# PSU12V-250mA-Protection.net
KiCad netlist of a schematic drawn in Altium Designer
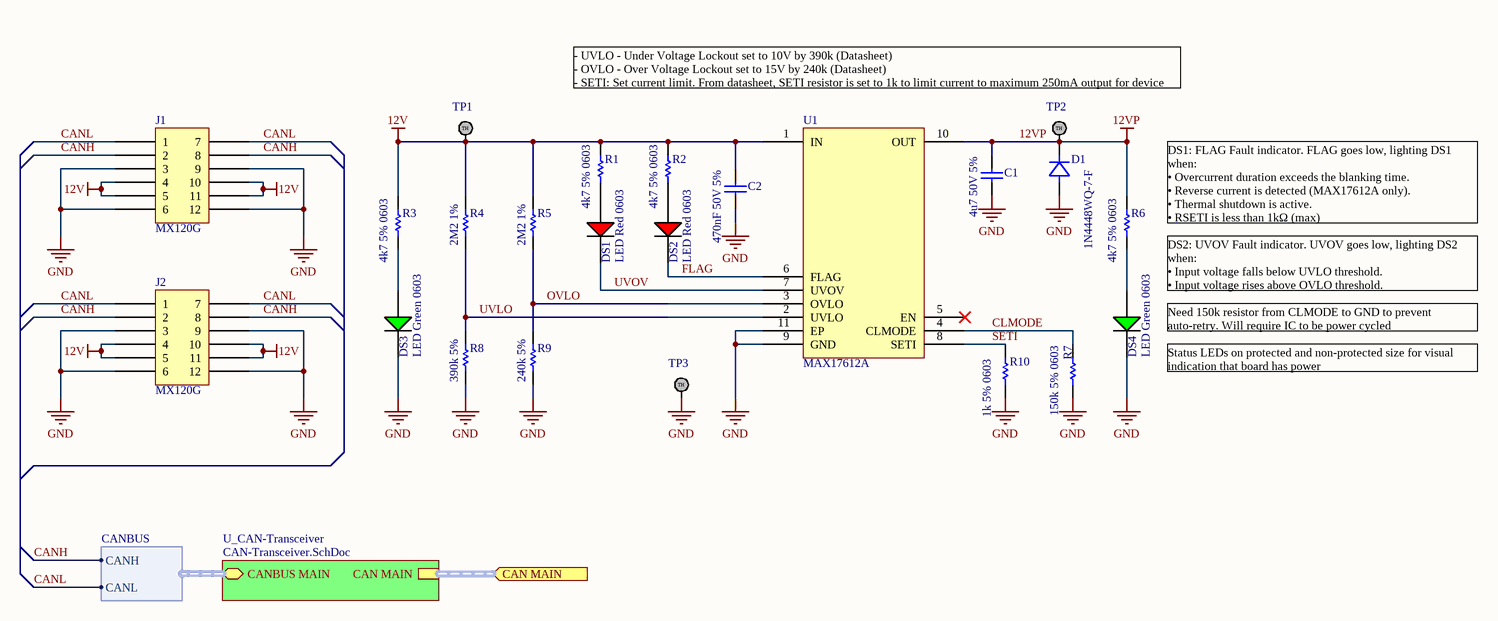
[diagram p0: PSU12V-250mA-Protection.SchDoc]

(export (version "E")
  (design (tool "Eeschema 10.0.6"))
  (components
    (comp (ref "C1")
      (value "4u7 50V 5%")
      (footprint "Cap_Ceramic_0603")
      (description "Capacitor, Ceramic, SMD, 4u7, 50V, 5%, X7R, 0603")
      (libsource (lib "StandardCapacitors") (part "4u7 50V 5% X7R 0603"))
    )
    (comp (ref "C2")
      (value "470nF 50V 5%")
      (footprint "Cap_Ceramic_0603")
      (description "Capacitor, Ceramic, SMD, 470nF, 50V, 5%, X7R, 0603")
      (libsource (lib "StandardCapacitors") (part "470nF 50V 5% X7R 0603"))
    )
    (comp (ref "D1")
      (value "1N4448WQ-7-F")
      (footprint "SMA")
      (description "Diode, SMD, 75V, 5%, 250mA, SOD123")
      (fields
        (field (name "MANUFACTURER") "ON Semiconductor / Fairchild")
        (field (name "MANUFACTURER PART NUMBER") "1N914BWS")
      )
      (libsource (lib "QUTMS_DiodeLibrary") (part "1N4448WQ-7-F"))
    )
    (comp (ref "DS1")
      (value "LED Red 0603")
      (footprint "LED RED 0603")
      (libsource (lib "QUTMS_LEDLibrary") (part "LED Red 0603"))
    )
    (comp (ref "DS2")
      (value "LED Red 0603")
      (footprint "LED RED 0603")
      (libsource (lib "QUTMS_LEDLibrary") (part "LED Red 0603"))
    )
    (comp (ref "DS3")
      (value "LED Green 0603")
      (footprint "LED GREEN 0603")
      (libsource (lib "QUTMS_LEDLibrary") (part "LED Green 0603"))
    )
    (comp (ref "DS4")
      (value "LED Green 0603")
      (footprint "LED GREEN 0603")
      (libsource (lib "QUTMS_LEDLibrary") (part "LED Green 0603"))
    )
    (comp (ref "J1")
      (value "MX120G")
      (footprint "MX120G")
      (description "MX120G with standard connector layout")
      (libsource (lib "QUTMS_MolexLibrary") (part "MX120G"))
    )
    (comp (ref "J2")
      (value "MX120G")
      (footprint "MX120G")
      (description "MX120G with standard connector layout")
      (libsource (lib "QUTMS_MolexLibrary") (part "MX120G"))
    )
    (comp (ref "R1")
      (value "4k7 5% 0603")
      (footprint "Res_ThinFilm_0603")
      (description "Resistor, SMD, 4k7, 0.1W, 5%, 0603")
      (libsource (lib "StandardResistors") (part "4k7 5% 0603"))
    )
    (comp (ref "R2")
      (value "4k7 5% 0603")
      (footprint "Res_ThinFilm_0603")
      (description "Resistor, SMD, 4k7, 0.1W, 5%, 0603")
      (libsource (lib "StandardResistors") (part "4k7 5% 0603"))
    )
    (comp (ref "R3")
      (value "4k7 5% 0603")
      (footprint "Res_ThinFilm_0603")
      (description "Resistor, SMD, 4k7, 0.1W, 5%, 0603")
      (libsource (lib "StandardResistors") (part "4k7 5% 0603"))
    )
    (comp (ref "R4")
      (value "2M2 1%")
      (footprint "Res_ThinFilm_0603")
      (description "Resistor, SMD, 2M2, 0.125W, 1%, 0603")
      (libsource (lib "StandardResistors") (part "2M2 1% 0603"))
    )
    (comp (ref "R5")
      (value "2M2 1%")
      (footprint "Res_ThinFilm_0603")
      (description "Resistor, SMD, 2M2, 0.125W, 1%, 0603")
      (libsource (lib "StandardResistors") (part "2M2 1% 0603"))
    )
    (comp (ref "R6")
      (value "4k7 5% 0603")
      (footprint "Res_ThinFilm_0603")
      (description "Resistor, SMD, 4k7, 0.1W, 5%, 0603")
      (libsource (lib "StandardResistors") (part "4k7 5% 0603"))
    )
    (comp (ref "R7")
      (value "150k 5% 0603")
      (footprint "Res_ThinFilm_0603")
      (description "Resistor, SMD, 150k, 0.1W, 5%, 0603")
      (libsource (lib "StandardResistors") (part "150k 5%, 0603"))
    )
    (comp (ref "R8")
      (value "390k 5%")
      (footprint "Res_ThinFilm_0603")
      (description "Resistor, SMD, 390k, 0.1W, 5%, 0603")
      (libsource (lib "StandardResistors") (part "390k 5% 0603"))
    )
    (comp (ref "R9")
      (value "240k 5%")
      (footprint "Res_ThinFilm_0603")
      (description "Resistor, SMD, 240k, 0.1W, 5%, 0603")
      (libsource (lib "StandardResistors") (part "240k 5% 0603"))
    )
    (comp (ref "R10")
      (value "1k 5% 0603")
      (footprint "Res_ThinFilm_0603")
      (description "Resistor, SMD, 1k, 0.1W, 5%, 0603")
      (libsource (lib "StandardResistors") (part "1k 5% 0603"))
    )
    (comp (ref "TP1")
      (value "TestPoint")
      (footprint "TestPoint")
      (libsource (lib "StandardTest") (part "TestPoint"))
    )
    (comp (ref "TP2")
      (value "TestPoint")
      (footprint "TestPoint")
      (libsource (lib "StandardTest") (part "TestPoint"))
    )
    (comp (ref "TP3")
      (value "TestPoint")
      (footprint "TestPoint")
      (libsource (lib "StandardTest") (part "TestPoint"))
    )
    (comp (ref "U1")
      (value "MAX17612A")
      (footprint "10-Pin TDFN EP")
      (description "4.5V to 60V, 250mA Current-Limiter with OV, UV, and Reverse Protection")
      (libsource (lib "QUTMS_IntegratedCircuitLibrary") (part "MAX17612A"))
    )
  )
  (nets
    (net (code "4") (name "/CANH") (class "Default")
      (node (ref "J1") (pin "2") (pinfunction "2_2") (pintype "passive"))
      (node (ref "J1") (pin "8") (pinfunction "8_8") (pintype "passive"))
      (node (ref "J2") (pin "2") (pinfunction "2_2") (pintype "passive"))
      (node (ref "J2") (pin "8") (pinfunction "8_8") (pintype "passive"))
    )
    (net (code "5") (name "/CANL") (class "Default")
      (node (ref "J1") (pin "1") (pinfunction "1_1") (pintype "passive"))
      (node (ref "J1") (pin "7") (pinfunction "7_7") (pintype "passive"))
      (node (ref "J2") (pin "1") (pinfunction "1_1") (pintype "passive"))
      (node (ref "J2") (pin "7") (pinfunction "7_7") (pintype "passive"))
    )
    (net (code "6") (name "/CLMODE") (class "Default")
      (node (ref "R7") (pin "2") (pinfunction "2_2") (pintype "passive"))
      (node (ref "U1") (pin "4") (pinfunction "CLMODE_4") (pintype "passive"))
    )
    (net (code "7") (name "/FLAG") (class "Default")
      (node (ref "DS2") (pin "2") (pinfunction "C_2") (pintype "passive"))
      (node (ref "U1") (pin "6") (pinfunction "FLAG_6") (pintype "passive"))
    )
    (net (code "8") (name "/OVLO") (class "Default")
      (node (ref "R5") (pin "1") (pinfunction "1_1") (pintype "passive"))
      (node (ref "R9") (pin "2") (pinfunction "2_2") (pintype "passive"))
      (node (ref "U1") (pin "3") (pinfunction "OVLO_3") (pintype "passive"))
    )
    (net (code "9") (name "/SETI") (class "Default")
      (node (ref "R10") (pin "2") (pinfunction "2_2") (pintype "passive"))
      (node (ref "U1") (pin "8") (pinfunction "SETI_8") (pintype "passive"))
    )
    (net (code "10") (name "/UVLO") (class "Default")
      (node (ref "R4") (pin "1") (pinfunction "1_1") (pintype "passive"))
      (node (ref "R8") (pin "2") (pinfunction "2_2") (pintype "passive"))
      (node (ref "U1") (pin "2") (pinfunction "UVLO_2") (pintype "passive"))
    )
    (net (code "11") (name "/UVOV") (class "Default")
      (node (ref "DS1") (pin "2") (pinfunction "C_2") (pintype "passive"))
      (node (ref "U1") (pin "7") (pinfunction "UVOV_7") (pintype "passive"))
    )
    (net (code "13") (name "12V") (class "Default")
      (node (ref "C2") (pin "2") (pinfunction "2_2") (pintype "passive"))
      (node (ref "J1") (pin "10") (pinfunction "10_10") (pintype "passive"))
      (node (ref "J1") (pin "11") (pinfunction "11_11") (pintype "passive"))
      (node (ref "J1") (pin "4") (pinfunction "4_4") (pintype "passive"))
      (node (ref "J1") (pin "5") (pinfunction "5_5") (pintype "passive"))
      (node (ref "J2") (pin "10") (pinfunction "10_10") (pintype "passive"))
      (node (ref "J2") (pin "11") (pinfunction "11_11") (pintype "passive"))
      (node (ref "J2") (pin "4") (pinfunction "4_4") (pintype "passive"))
      (node (ref "J2") (pin "5") (pinfunction "5_5") (pintype "passive"))
      (node (ref "R1") (pin "2") (pinfunction "2_2") (pintype "passive"))
      (node (ref "R2") (pin "2") (pinfunction "2_2") (pintype "passive"))
      (node (ref "R3") (pin "2") (pinfunction "2_2") (pintype "passive"))
      (node (ref "R4") (pin "2") (pinfunction "2_2") (pintype "passive"))
      (node (ref "R5") (pin "2") (pinfunction "2_2") (pintype "passive"))
      (node (ref "TP1") (pin "1") (pinfunction "1_1") (pintype "passive"))
      (node (ref "U1") (pin "1") (pinfunction "IN_1") (pintype "passive"))
    )
    (net (code "14") (name "12VP") (class "Default")
      (node (ref "C1") (pin "2") (pinfunction "2_2") (pintype "passive"))
      (node (ref "D1") (pin "K") (pinfunction "Cathode_K") (pintype "passive"))
      (node (ref "R6") (pin "2") (pinfunction "2_2") (pintype "passive"))
      (node (ref "TP2") (pin "1") (pinfunction "1_1") (pintype "passive"))
      (node (ref "U1") (pin "10") (pinfunction "OUT_10") (pintype "passive"))
    )
    (net (code "15") (name "GND") (class "Default")
      (node (ref "C1") (pin "1") (pinfunction "1_1") (pintype "passive"))
      (node (ref "C2") (pin "1") (pinfunction "1_1") (pintype "passive"))
      (node (ref "D1") (pin "A") (pinfunction "Anode_A") (pintype "passive"))
      (node (ref "DS3") (pin "2") (pinfunction "C_2") (pintype "passive"))
      (node (ref "DS4") (pin "2") (pinfunction "C_2") (pintype "passive"))
      (node (ref "J1") (pin "12") (pinfunction "12_12") (pintype "passive"))
      (node (ref "J1") (pin "3") (pinfunction "3_3") (pintype "passive"))
      (node (ref "J1") (pin "6") (pinfunction "6_6") (pintype "passive"))
      (node (ref "J1") (pin "9") (pinfunction "9_9") (pintype "passive"))
      (node (ref "J2") (pin "12") (pinfunction "12_12") (pintype "passive"))
      (node (ref "J2") (pin "3") (pinfunction "3_3") (pintype "passive"))
      (node (ref "J2") (pin "6") (pinfunction "6_6") (pintype "passive"))
      (node (ref "J2") (pin "9") (pinfunction "9_9") (pintype "passive"))
      (node (ref "R10") (pin "1") (pinfunction "1_1") (pintype "passive"))
      (node (ref "R7") (pin "1") (pinfunction "1_1") (pintype "passive"))
      (node (ref "R8") (pin "1") (pinfunction "1_1") (pintype "passive"))
      (node (ref "R9") (pin "1") (pinfunction "1_1") (pintype "passive"))
      (node (ref "TP3") (pin "1") (pinfunction "1_1") (pintype "passive"))
      (node (ref "U1") (pin "11") (pinfunction "EP_11") (pintype "passive"))
      (node (ref "U1") (pin "9") (pinfunction "GND_9") (pintype "passive"))
    )
    (net (code "16") (name "Net-(DS1-A)") (class "Default")
      (node (ref "DS1") (pin "1") (pinfunction "A_1") (pintype "passive"))
      (node (ref "R1") (pin "1") (pinfunction "1_1") (pintype "passive"))
    )
    (net (code "17") (name "Net-(DS2-A)") (class "Default")
      (node (ref "DS2") (pin "1") (pinfunction "A_1") (pintype "passive"))
      (node (ref "R2") (pin "1") (pinfunction "1_1") (pintype "passive"))
    )
    (net (code "18") (name "Net-(DS3-A)") (class "Default")
      (node (ref "DS3") (pin "1") (pinfunction "A_1") (pintype "passive"))
      (node (ref "R3") (pin "1") (pinfunction "1_1") (pintype "passive"))
    )
    (net (code "19") (name "Net-(DS4-A)") (class "Default")
      (node (ref "DS4") (pin "1") (pinfunction "A_1") (pintype "passive"))
      (node (ref "R6") (pin "1") (pinfunction "1_1") (pintype "passive"))
    )
    (net (code "20") (name "unconnected-(U1-EN-Pad5)") (class "Default")
      (node (ref "U1") (pin "5") (pinfunction "EN_5") (pintype "passive+no_connect"))
    )
  )
)
